# dcdc_60v_12v.net
KiCad netlist of a schematic drawn in Altium Designer
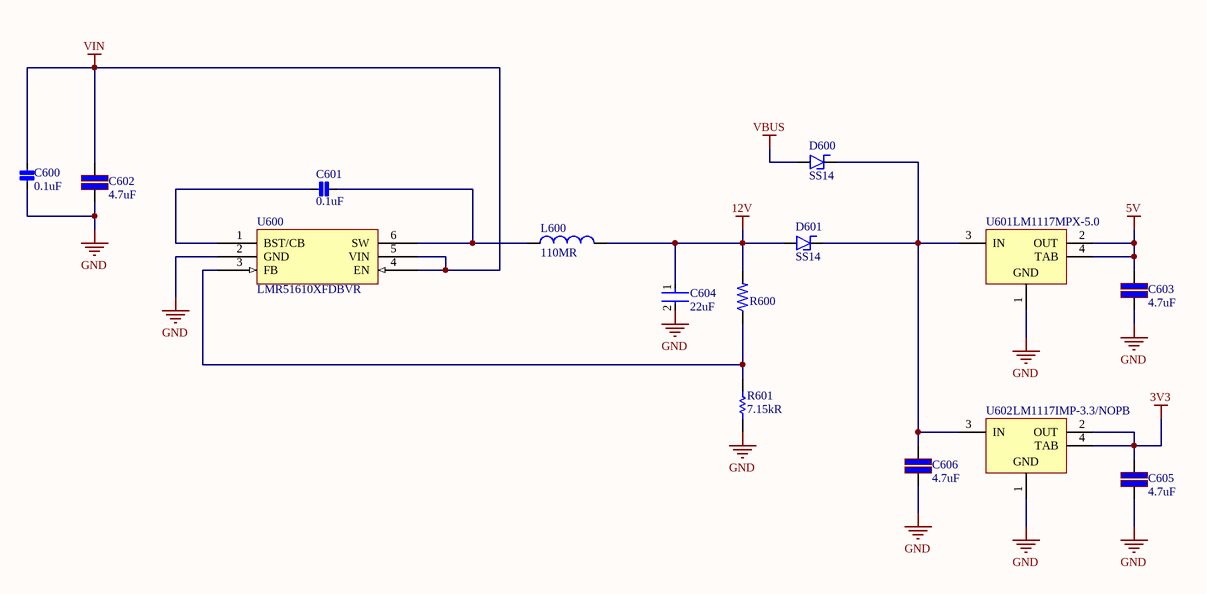
[diagram p0: dcdc_60v_12v.SchDoc]

(export (version "E")
  (design (tool "Eeschema 10.0.6"))
  (components
    (comp (ref "C600")
      (value "0.1uF")
      (footprint "FP-CL10-IPC_B")
      (description "Cap Ceramic 0.1uF 50V X7R 20% SMD 0603 125C Paper T/R")
      (fields (field (name "VOLTAGE") "50V") (field (name "Comment") "CAP 0.1uF 50V X7R 0603"))
      (libsource (lib "StackFoundry LLC") (part "C-EU"))
    )
    (comp (ref "C601")
      (value "0.1uF")
      (footprint "FP-CL10-IPC_B")
      (description "Cap Ceramic 0.1uF 50V X7R 20% SMD 0603 125C Paper T/R")
      (fields (field (name "VOLTAGE") "50V") (field (name "Comment") "CAP 0.1uF 50V X7R 0603"))
      (libsource (lib "") (part "C-EU_1"))
    )
    (comp (ref "C602")
      (value "4.7uF")
      (footprint "CAPC3225X20N")
      (description "CAP CER 4.7UF 50V X7R 1210")
      (fields (field (name "VOLTAGE") "50V") (field (name "TOLERANCE") "10%"))
      (libsource (lib "StackFoundry LLC") (part "4.7uF"))
    )
    (comp (ref "C603")
      (value "4.7uF")
      (footprint "CAPC3225X20N")
      (description "CAP CER 4.7UF 50V X7R 1210")
      (fields (field (name "VOLTAGE") "50V") (field (name "TOLERANCE") "10%"))
      (libsource (lib "StackFoundry LLC") (part "4.7uF"))
    )
    (comp (ref "C604")
      (value "22uF")
      (footprint "FP-1210-L_3_2_0_3-W_2_5_0-MFG")
      (description "1210 22 uF 25 V ±20% Tolerance X7R Multilayer Ceramic Chip Capacitor")
      (fields (field (name "TOLERANCE") "20%") (field (name "Comment") "CAP 22uF 25V 1210 X7R"))
      (libsource (lib "StackFoundry LLC") (part "02cd4be3c70576c341d710602a673aa"))
    )
    (comp (ref "C605")
      (value "4.7uF")
      (footprint "CAPC3225X20N")
      (description "CAP CER 4.7UF 50V X7R 1210")
      (fields (field (name "VOLTAGE") "50V") (field (name "TOLERANCE") "10%"))
      (libsource (lib "StackFoundry LLC") (part "4.7uF"))
    )
    (comp (ref "C606")
      (value "4.7uF")
      (footprint "CAPC3225X20N")
      (description "CAP CER 4.7UF 50V X7R 1210")
      (fields (field (name "VOLTAGE") "50V") (field (name "TOLERANCE") "10%"))
      (libsource (lib "StackFoundry LLC") (part "4.7uF"))
    )
    (comp (ref "D600")
      (value "SS14")
      (footprint "SMA")
      (libsource (lib "StackFoundry LLC") (part "DIODE_SCHOTTKY"))
    )
    (comp (ref "D601")
      (value "SS14")
      (footprint "SMA")
      (libsource (lib "StackFoundry LLC") (part "DIODE_SCHOTTKY"))
    )
    (comp (ref "L600")
      (value "110MR")
      (footprint "SRR1260-680M-Footprint-1")
      (description "Ind Power Shielded Wirewound 68uH 20% 100KHz 22Q-Factor Ferrite 2.1A T/R")
      (fields (field (name "TOLERANCE") "20%") (field (name "Comment") "SRR1260-680M"))
      (libsource (lib "StackFoundry LLC") (part "L-US"))
    )
    (comp (ref "R600")
      (value "100k 0603 1%")
      (footprint "RESC1608-IPC-LL")
      (description "Res Thick Film 1.6 x 0.8 mm 100K Ohm 1% 0.1W(1/10W) 100ppm/ C Molded SMD Paper T/R")
      (libsource (lib "StackFoundry LLC") (part "R-US"))
    )
    (comp (ref "R601")
      (value "7.15kR")
      (footprint "RESC1608X55X30NL20T20")
      (description "Res Thin Film 0603 7.15K Ohm 0.1% 1/10W ±25ppm/°C Molded SMD SMD Punched Carrier T/R")
      (fields (field (name "Comment") "7.15k 0603 0.1%"))
      (libsource (lib "StackFoundry LLC") (part "RES"))
    )
    (comp (ref "U600")
      (value "LMR51610XFDBVR")
      (footprint "SOT95P280X145-6N")
      (libsource (lib "StackFoundry LLC") (part "LMR51610XFDBVR-Symbol-1"))
    )
    (comp (ref "U601")
      (value "LM1117MPX-5.0")
      (footprint "DCY0004A_M")
      (description "LDO Regulator Pos 5V 0.8A 4-Pin(3+Tab) SOT-223 T/R")
      (libsource (lib "StackFoundry LLC") (part "PM-REG-LM1086-SOT4"))
    )
    (comp (ref "U602")
      (value "LM1117IMP-3.3/NOPB")
      (footprint "DCY0004A_M")
      (description "LDO Regulator Pos 3.3V 0.8A 4-Pin(3+Tab) SOT-223 T/R / IC REG LDO 3.3V 0.8A SOT223")
      (libsource (lib "StackFoundry LLC") (part "PM-REG-LM1086-SOT4"))
    )
  )
  (nets
    (net (code "1") (name "3V3") (class "Default")
      (node (ref "C605") (pin "2") (pintype "passive"))
      (node (ref "U602") (pin "2") (pinfunction "OUT_2") (pintype "power_in"))
      (node (ref "U602") (pin "4") (pinfunction "TAB_4") (pintype "power_in"))
    )
    (net (code "2") (name "5V") (class "Default")
      (node (ref "C603") (pin "2") (pintype "passive"))
      (node (ref "U601") (pin "2") (pinfunction "OUT_2") (pintype "power_in"))
      (node (ref "U601") (pin "4") (pinfunction "TAB_4") (pintype "power_in"))
    )
    (net (code "3") (name "12V") (class "Default")
      (node (ref "C604") (pin "1") (pinfunction "1_1") (pintype "passive"))
      (node (ref "D601") (pin "A") (pinfunction "A_A") (pintype "power_in"))
      (node (ref "L600") (pin "2") (pinfunction "2_2") (pintype "passive"))
      (node (ref "R600") (pin "2") (pinfunction "2_2") (pintype "passive"))
    )
    (net (code "4") (name "GND") (class "Default")
      (node (ref "C600") (pin "1") (pinfunction "1_1") (pintype "passive"))
      (node (ref "C602") (pin "1") (pintype "passive"))
      (node (ref "C603") (pin "1") (pintype "passive"))
      (node (ref "C604") (pin "2") (pinfunction "2_2") (pintype "passive"))
      (node (ref "C605") (pin "1") (pintype "passive"))
      (node (ref "C606") (pin "1") (pintype "passive"))
      (node (ref "R601") (pin "1") (pinfunction "1_1") (pintype "passive"))
      (node (ref "U600") (pin "2") (pinfunction "GND_2") (pintype "power_in"))
      (node (ref "U601") (pin "1") (pinfunction "GND_1") (pintype "power_in"))
      (node (ref "U602") (pin "1") (pinfunction "GND_1") (pintype "power_in"))
    )
    (net (code "5") (name "Net-(U600-BST{slash}CB)") (class "Default")
      (node (ref "C601") (pin "1") (pinfunction "1_1") (pintype "passive"))
      (node (ref "U600") (pin "1") (pinfunction "BST/CB_1") (pintype "passive"))
    )
    (net (code "6") (name "Net-(U600-FB)") (class "Default")
      (node (ref "R600") (pin "1") (pinfunction "1_1") (pintype "passive"))
      (node (ref "R601") (pin "2") (pinfunction "2_2") (pintype "passive"))
      (node (ref "U600") (pin "3") (pinfunction "FB_3") (pintype "input"))
    )
    (net (code "7") (name "Net-(U600-SW)") (class "Default")
      (node (ref "C601") (pin "2") (pinfunction "2_2") (pintype "passive"))
      (node (ref "L600") (pin "1") (pinfunction "1_1") (pintype "passive"))
      (node (ref "U600") (pin "6") (pinfunction "SW_6") (pintype "passive"))
    )
    (net (code "8") (name "Net-(U601-IN)") (class "Default")
      (node (ref "C606") (pin "2") (pintype "passive"))
      (node (ref "D600") (pin "K") (pinfunction "K_K") (pintype "power_in"))
      (node (ref "D601") (pin "K") (pinfunction "K_K") (pintype "power_in"))
      (node (ref "U601") (pin "3") (pinfunction "IN_3") (pintype "power_in"))
      (node (ref "U602") (pin "3") (pinfunction "IN_3") (pintype "power_in"))
    )
    (net (code "9") (name "VBUS") (class "Default")
      (node (ref "D600") (pin "A") (pinfunction "A_A") (pintype "power_in"))
    )
    (net (code "10") (name "VIN") (class "Default")
      (node (ref "C600") (pin "2") (pinfunction "2_2") (pintype "passive"))
      (node (ref "C602") (pin "2") (pintype "passive"))
      (node (ref "U600") (pin "4") (pinfunction "EN_4") (pintype "input"))
      (node (ref "U600") (pin "5") (pinfunction "VIN_5") (pintype "power_in"))
    )
  )
)
